# Private_CPU_IO.net
KiCad netlist of a schematic drawn in Altium Designer
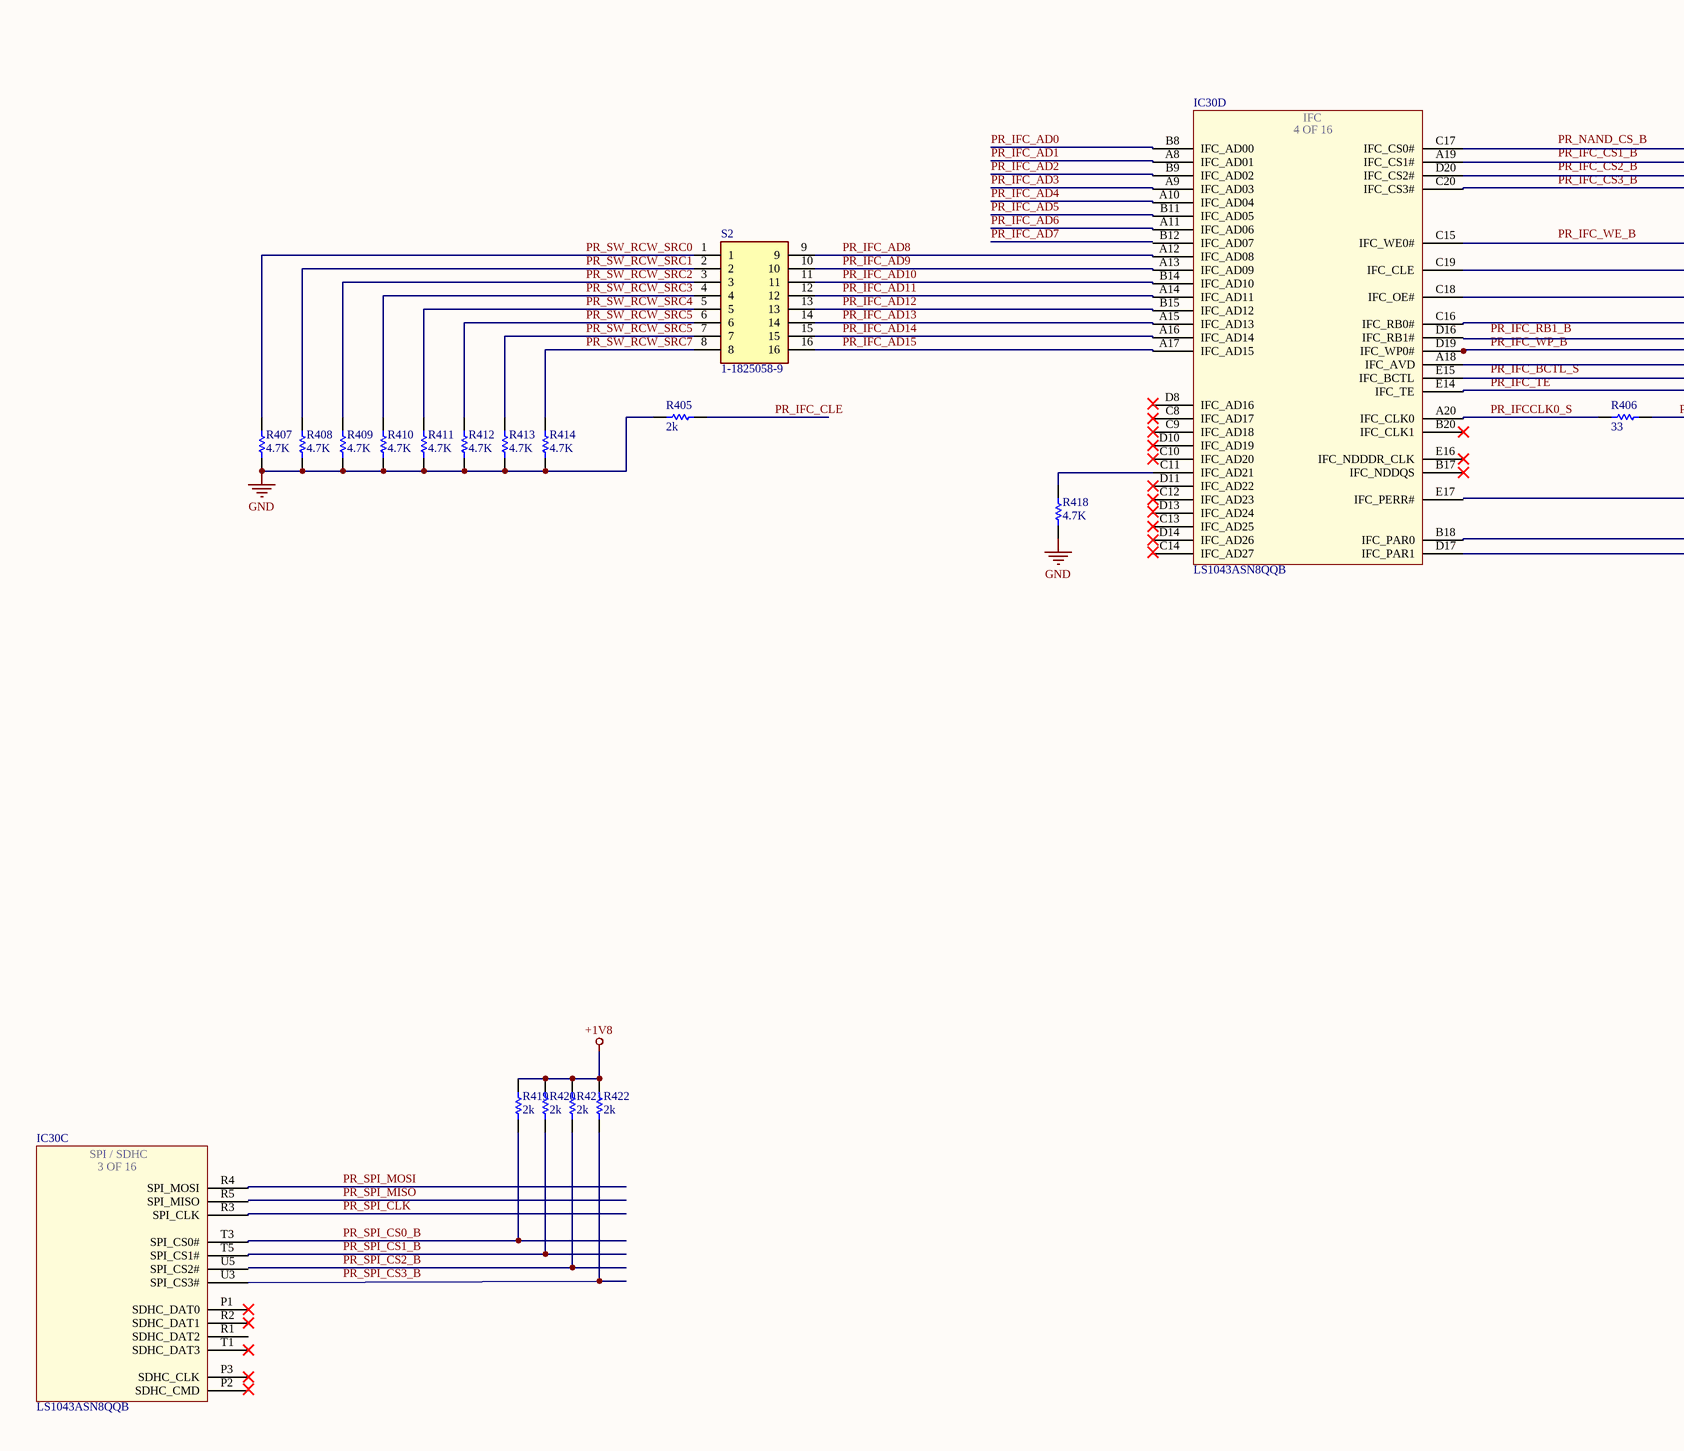
[diagram p0: Private_CPU_IO.SchDoc, left]
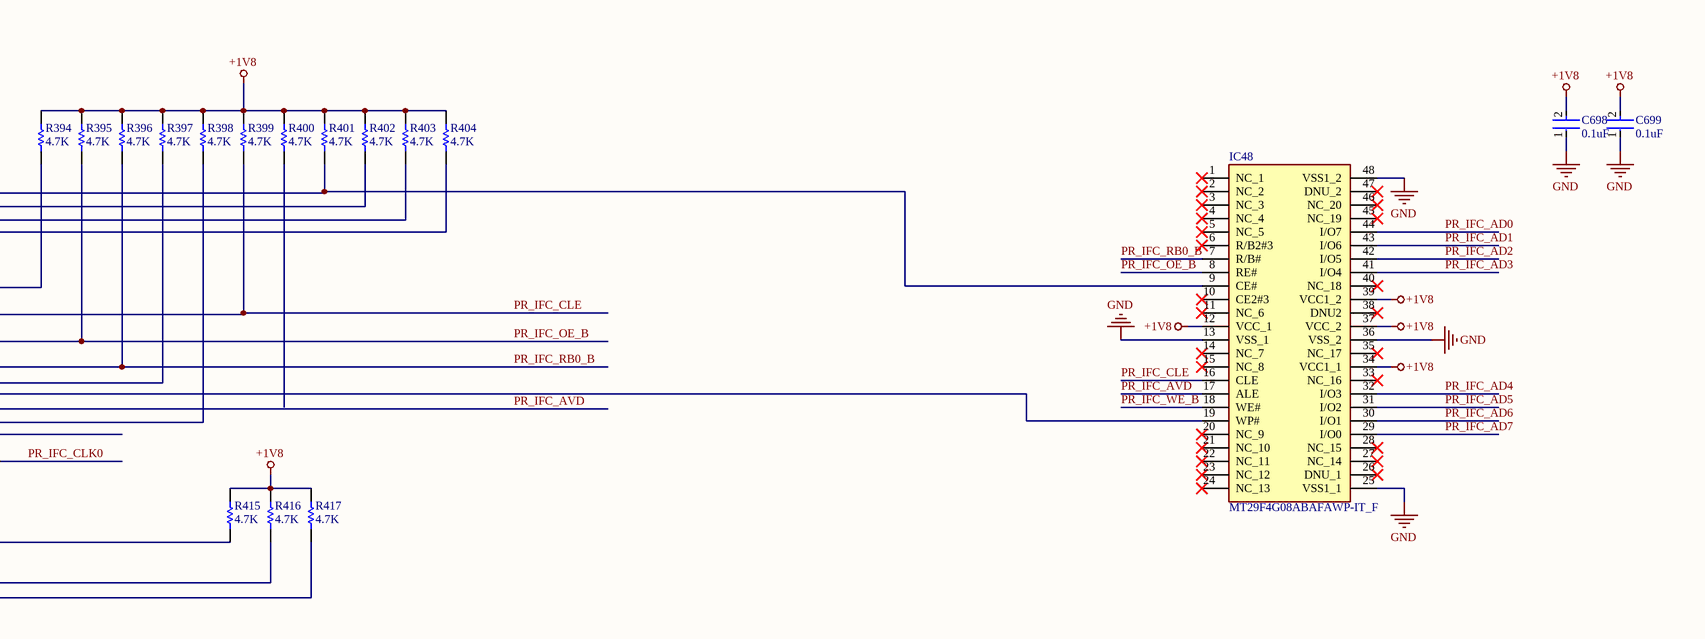
[diagram p1: Private_CPU_IO.SchDoc, right]

(export (version "E")
  (design (tool "Eeschema 10.0.6"))
  (components
    (comp (ref "C698")
      (value "0.1uF")
      (footprint "FP-GRM15-MFG")
      (description "CAP CER 0.1UF 16V X7R 0402")
      (fields (field (name "MANUFACTURER PART NUMBER") "GRM155R71C104KA88D") (field (name "TOLERANCE") "10%"))
      (libsource (lib "Altium Content Vault") (part "236180d848d6139a670b325ea6854c9"))
    )
    (comp (ref "C699")
      (value "0.1uF")
      (footprint "FP-GRM15-MFG")
      (description "CAP CER 0.1UF 16V X7R 0402")
      (fields (field (name "MANUFACTURER PART NUMBER") "GRM155R71C104KA88D") (field (name "TOLERANCE") "10%"))
      (libsource (lib "Altium Content Vault") (part "236180d848d6139a670b325ea6854c9"))
    )
    (comp (ref "IC30")
      (value "LS1043ASN8QQB")
      (footprint "SamacSys:BGA780C80P28X28_2300X2300X261")
      (description "Integrated Circuit")
      (fields (field (name "MOUSER PART NUMBER") "771-LS1043ASN8QQB"))
      (libsource (lib "SamacSys") (part "LS1043ASN8QQB"))
    )
    (comp (ref "IC48")
      (value "MT29F4G08ABAFAWP-IT_F")
      (footprint "SamacSys:SOP50P2000X120-48N")
      (description "Integrated Circuit")
      (fields
        (field (name "MANUFACTURER_PART_NUMBER") "MT29F4G08ABAFAWP-IT:F")
        (field (name "MOUSER PART NUMBER") "340-371016-TRAY")
      )
      (libsource (lib "*") (part "MT29F4G08ABAFAWP-IT_F"))
    )
    (comp (ref "R394")
      (value "4.7K")
      (footprint "RESC1005X40X25LL05T05")
      (description "Chip Resistor, 4.7 KOhm, +/- 1%, 0.1 W, -55 to 155 degC, 0402 (1005 Metric), RoHS, Tape and Reel")
      (fields (field (name "TOLERANCE") "1%") (field (name "PARTNUMBER") "ERJ-2RKF4701X"))
      (libsource (lib "Altium Content Vault") (part "RES-2"))
    )
    (comp (ref "R395")
      (value "4.7K")
      (footprint "RESC1005X40X25LL05T05")
      (description "Chip Resistor, 4.7 KOhm, +/- 1%, 0.1 W, -55 to 155 degC, 0402 (1005 Metric), RoHS, Tape and Reel")
      (fields (field (name "TOLERANCE") "1%") (field (name "PARTNUMBER") "ERJ-2RKF4701X"))
      (libsource (lib "Altium Content Vault") (part "RES-2"))
    )
    (comp (ref "R396")
      (value "4.7K")
      (footprint "RESC1005X40X25LL05T05")
      (description "Chip Resistor, 4.7 KOhm, +/- 1%, 0.1 W, -55 to 155 degC, 0402 (1005 Metric), RoHS, Tape and Reel")
      (fields (field (name "TOLERANCE") "1%") (field (name "PARTNUMBER") "ERJ-2RKF4701X"))
      (libsource (lib "Altium Content Vault") (part "RES-2"))
    )
    (comp (ref "R397")
      (value "4.7K")
      (footprint "RESC1005X40X25LL05T05")
      (description "Chip Resistor, 4.7 KOhm, +/- 1%, 0.1 W, -55 to 155 degC, 0402 (1005 Metric), RoHS, Tape and Reel")
      (fields (field (name "TOLERANCE") "1%") (field (name "PARTNUMBER") "ERJ-2RKF4701X"))
      (libsource (lib "Altium Content Vault") (part "RES-2"))
    )
    (comp (ref "R398")
      (value "4.7K")
      (footprint "RESC1005X40X25LL05T05")
      (description "Chip Resistor, 4.7 KOhm, +/- 1%, 0.1 W, -55 to 155 degC, 0402 (1005 Metric), RoHS, Tape and Reel")
      (fields (field (name "TOLERANCE") "1%") (field (name "PARTNUMBER") "ERJ-2RKF4701X"))
      (libsource (lib "Altium Content Vault") (part "RES-2"))
    )
    (comp (ref "R399")
      (value "4.7K")
      (footprint "RESC1005X40X25LL05T05")
      (description "Chip Resistor, 4.7 KOhm, +/- 1%, 0.1 W, -55 to 155 degC, 0402 (1005 Metric), RoHS, Tape and Reel")
      (fields (field (name "TOLERANCE") "1%") (field (name "PARTNUMBER") "ERJ-2RKF4701X"))
      (libsource (lib "Altium Content Vault") (part "RES-2"))
    )
    (comp (ref "R400")
      (value "4.7K")
      (footprint "RESC1005X40X25LL05T05")
      (description "Chip Resistor, 4.7 KOhm, +/- 1%, 0.1 W, -55 to 155 degC, 0402 (1005 Metric), RoHS, Tape and Reel")
      (fields (field (name "TOLERANCE") "1%") (field (name "PARTNUMBER") "ERJ-2RKF4701X"))
      (libsource (lib "Altium Content Vault") (part "RES-2"))
    )
    (comp (ref "R401")
      (value "4.7K")
      (footprint "RESC1005X40X25LL05T05")
      (description "Chip Resistor, 4.7 KOhm, +/- 1%, 0.1 W, -55 to 155 degC, 0402 (1005 Metric), RoHS, Tape and Reel")
      (fields (field (name "TOLERANCE") "1%") (field (name "PARTNUMBER") "ERJ-2RKF4701X"))
      (libsource (lib "Altium Content Vault") (part "RES-2"))
    )
    (comp (ref "R402")
      (value "4.7K")
      (footprint "RESC1005X40X25LL05T05")
      (description "Chip Resistor, 4.7 KOhm, +/- 1%, 0.1 W, -55 to 155 degC, 0402 (1005 Metric), RoHS, Tape and Reel")
      (fields (field (name "TOLERANCE") "1%") (field (name "PARTNUMBER") "ERJ-2RKF4701X"))
      (libsource (lib "Altium Content Vault") (part "RES-2"))
    )
    (comp (ref "R403")
      (value "4.7K")
      (footprint "RESC1005X40X25LL05T05")
      (description "Chip Resistor, 4.7 KOhm, +/- 1%, 0.1 W, -55 to 155 degC, 0402 (1005 Metric), RoHS, Tape and Reel")
      (fields (field (name "TOLERANCE") "1%") (field (name "PARTNUMBER") "ERJ-2RKF4701X"))
      (libsource (lib "Altium Content Vault") (part "RES-2"))
    )
    (comp (ref "R404")
      (value "4.7K")
      (footprint "RESC1005X40X25LL05T05")
      (description "Chip Resistor, 4.7 KOhm, +/- 1%, 0.1 W, -55 to 155 degC, 0402 (1005 Metric), RoHS, Tape and Reel")
      (fields (field (name "TOLERANCE") "1%") (field (name "PARTNUMBER") "ERJ-2RKF4701X"))
      (libsource (lib "Altium Content Vault") (part "RES-2"))
    )
    (comp (ref "R405")
      (value "2k")
      (footprint "RESC1005X40X25NL05T05")
      (description "Chip Resistor, 2 KOhm, +/- 1%, 100 mW, -55 to 155 degC, 0402 (1005 Metric), RoHS, Tape and Reel")
      (fields (field (name "MANUFACTURER") "Basic Passives") (field (name "TOLERANCE") "1%"))
      (libsource (lib "Altium Content Vault") (part "RES-2"))
    )
    (comp (ref "R406")
      (value "33")
      (footprint "RESC1005X40X25LL05T05")
      (fields (field (name "MANUFACTURER") "Panasonic") (field (name "PART NUMBER") "ERJ2RKF33R0X"))
      (libsource (lib "Altium Content Vault") (part "RES"))
    )
    (comp (ref "R407")
      (value "4.7K")
      (footprint "RESC1005X40X25LL05T05")
      (description "Chip Resistor, 4.7 KOhm, +/- 1%, 0.1 W, -55 to 155 degC, 0402 (1005 Metric), RoHS, Tape and Reel")
      (fields (field (name "TOLERANCE") "1%") (field (name "PARTNUMBER") "ERJ-2RKF4701X"))
      (libsource (lib "Altium Content Vault") (part "RES-2"))
    )
    (comp (ref "R408")
      (value "4.7K")
      (footprint "RESC1005X40X25LL05T05")
      (description "Chip Resistor, 4.7 KOhm, +/- 1%, 0.1 W, -55 to 155 degC, 0402 (1005 Metric), RoHS, Tape and Reel")
      (fields (field (name "TOLERANCE") "1%") (field (name "PARTNUMBER") "ERJ-2RKF4701X"))
      (libsource (lib "Altium Content Vault") (part "RES-2"))
    )
    (comp (ref "R409")
      (value "4.7K")
      (footprint "RESC1005X40X25LL05T05")
      (description "Chip Resistor, 4.7 KOhm, +/- 1%, 0.1 W, -55 to 155 degC, 0402 (1005 Metric), RoHS, Tape and Reel")
      (fields (field (name "TOLERANCE") "1%") (field (name "PARTNUMBER") "ERJ-2RKF4701X"))
      (libsource (lib "Altium Content Vault") (part "RES-2"))
    )
    (comp (ref "R410")
      (value "4.7K")
      (footprint "RESC1005X40X25LL05T05")
      (description "Chip Resistor, 4.7 KOhm, +/- 1%, 0.1 W, -55 to 155 degC, 0402 (1005 Metric), RoHS, Tape and Reel")
      (fields (field (name "TOLERANCE") "1%") (field (name "PARTNUMBER") "ERJ-2RKF4701X"))
      (libsource (lib "Altium Content Vault") (part "RES-2"))
    )
    (comp (ref "R411")
      (value "4.7K")
      (footprint "RESC1005X40X25LL05T05")
      (description "Chip Resistor, 4.7 KOhm, +/- 1%, 0.1 W, -55 to 155 degC, 0402 (1005 Metric), RoHS, Tape and Reel")
      (fields (field (name "TOLERANCE") "1%") (field (name "PARTNUMBER") "ERJ-2RKF4701X"))
      (libsource (lib "Altium Content Vault") (part "RES-2"))
    )
    (comp (ref "R412")
      (value "4.7K")
      (footprint "RESC1005X40X25LL05T05")
      (description "Chip Resistor, 4.7 KOhm, +/- 1%, 0.1 W, -55 to 155 degC, 0402 (1005 Metric), RoHS, Tape and Reel")
      (fields (field (name "TOLERANCE") "1%") (field (name "PARTNUMBER") "ERJ-2RKF4701X"))
      (libsource (lib "Altium Content Vault") (part "RES-2"))
    )
    (comp (ref "R413")
      (value "4.7K")
      (footprint "RESC1005X40X25LL05T05")
      (description "Chip Resistor, 4.7 KOhm, +/- 1%, 0.1 W, -55 to 155 degC, 0402 (1005 Metric), RoHS, Tape and Reel")
      (fields (field (name "TOLERANCE") "1%") (field (name "PARTNUMBER") "ERJ-2RKF4701X"))
      (libsource (lib "Altium Content Vault") (part "RES-2"))
    )
    (comp (ref "R414")
      (value "4.7K")
      (footprint "RESC1005X40X25LL05T05")
      (description "Chip Resistor, 4.7 KOhm, +/- 1%, 0.1 W, -55 to 155 degC, 0402 (1005 Metric), RoHS, Tape and Reel")
      (fields (field (name "TOLERANCE") "1%") (field (name "PARTNUMBER") "ERJ-2RKF4701X"))
      (libsource (lib "Altium Content Vault") (part "RES-2"))
    )
    (comp (ref "R415")
      (value "4.7K")
      (footprint "RESC1005X40X25LL05T05")
      (description "Chip Resistor, 4.7 KOhm, +/- 1%, 0.1 W, -55 to 155 degC, 0402 (1005 Metric), RoHS, Tape and Reel")
      (fields (field (name "TOLERANCE") "1%") (field (name "PARTNUMBER") "ERJ-2RKF4701X"))
      (libsource (lib "Altium Content Vault") (part "RES-2"))
    )
    (comp (ref "R416")
      (value "4.7K")
      (footprint "RESC1005X40X25LL05T05")
      (description "Chip Resistor, 4.7 KOhm, +/- 1%, 0.1 W, -55 to 155 degC, 0402 (1005 Metric), RoHS, Tape and Reel")
      (fields (field (name "TOLERANCE") "1%") (field (name "PARTNUMBER") "ERJ-2RKF4701X"))
      (libsource (lib "Altium Content Vault") (part "RES-2"))
    )
    (comp (ref "R417")
      (value "4.7K")
      (footprint "RESC1005X40X25LL05T05")
      (description "Chip Resistor, 4.7 KOhm, +/- 1%, 0.1 W, -55 to 155 degC, 0402 (1005 Metric), RoHS, Tape and Reel")
      (fields (field (name "TOLERANCE") "1%") (field (name "PARTNUMBER") "ERJ-2RKF4701X"))
      (libsource (lib "Altium Content Vault") (part "RES-2"))
    )
    (comp (ref "R418")
      (value "4.7K")
      (footprint "RESC1005X40X25LL05T05")
      (description "Chip Resistor, 4.7 KOhm, +/- 1%, 0.1 W, -55 to 155 degC, 0402 (1005 Metric), RoHS, Tape and Reel")
      (fields (field (name "TOLERANCE") "1%") (field (name "PARTNUMBER") "ERJ-2RKF4701X"))
      (libsource (lib "Altium Content Vault") (part "RES-2"))
    )
    (comp (ref "R419")
      (value "2k")
      (footprint "RESC1005X40X25NL05T05")
      (description "Chip Resistor, 2 KOhm, +/- 1%, 100 mW, -55 to 155 degC, 0402 (1005 Metric), RoHS, Tape and Reel")
      (fields (field (name "MANUFACTURER") "Basic Passives") (field (name "TOLERANCE") "1%"))
      (libsource (lib "Altium Content Vault") (part "RES-2"))
    )
    (comp (ref "R420")
      (value "2k")
      (footprint "RESC1005X40X25NL05T05")
      (description "Chip Resistor, 2 KOhm, +/- 1%, 100 mW, -55 to 155 degC, 0402 (1005 Metric), RoHS, Tape and Reel")
      (fields (field (name "MANUFACTURER") "Basic Passives") (field (name "TOLERANCE") "1%"))
      (libsource (lib "Altium Content Vault") (part "RES-2"))
    )
    (comp (ref "R421")
      (value "2k")
      (footprint "RESC1005X40X25NL05T05")
      (description "Chip Resistor, 2 KOhm, +/- 1%, 100 mW, -55 to 155 degC, 0402 (1005 Metric), RoHS, Tape and Reel")
      (fields (field (name "MANUFACTURER") "Basic Passives") (field (name "TOLERANCE") "1%"))
      (libsource (lib "Altium Content Vault") (part "RES-2"))
    )
    (comp (ref "R422")
      (value "2k")
      (footprint "RESC1005X40X25NL05T05")
      (description "Chip Resistor, 2 KOhm, +/- 1%, 100 mW, -55 to 155 degC, 0402 (1005 Metric), RoHS, Tape and Reel")
      (fields (field (name "MANUFACTURER") "Basic Passives") (field (name "TOLERANCE") "1%"))
      (libsource (lib "Altium Content Vault") (part "RES-2"))
    )
    (comp (ref "S2")
      (value "1-1825058-9")
      (footprint "SamacSys:118250589")
      (description "Switch")
      (libsource (lib "*") (part "1-1825058-9"))
    )
  )
  (nets
    (net (code "1") (name "+1V8") (class "Default")
      (node (ref "C698") (pin "2") (pinfunction "2_2") (pintype "passive"))
      (node (ref "C699") (pin "2") (pinfunction "2_2") (pintype "passive"))
      (node (ref "IC48") (pin "12") (pinfunction "VCC_1_12") (pintype "passive"))
      (node (ref "IC48") (pin "34") (pinfunction "VCC1_1_34") (pintype "passive"))
      (node (ref "IC48") (pin "37") (pinfunction "VCC_2_37") (pintype "passive"))
      (node (ref "IC48") (pin "39") (pinfunction "VCC1_2_39") (pintype "passive"))
      (node (ref "R394") (pin "2") (pinfunction "2_2") (pintype "passive"))
      (node (ref "R395") (pin "2") (pinfunction "2_2") (pintype "passive"))
      (node (ref "R396") (pin "2") (pinfunction "2_2") (pintype "passive"))
      (node (ref "R397") (pin "2") (pinfunction "2_2") (pintype "passive"))
      (node (ref "R398") (pin "2") (pinfunction "2_2") (pintype "passive"))
      (node (ref "R399") (pin "2") (pinfunction "2_2") (pintype "passive"))
      (node (ref "R400") (pin "2") (pinfunction "2_2") (pintype "passive"))
      (node (ref "R401") (pin "2") (pinfunction "2_2") (pintype "passive"))
      (node (ref "R402") (pin "2") (pinfunction "2_2") (pintype "passive"))
      (node (ref "R403") (pin "2") (pinfunction "2_2") (pintype "passive"))
      (node (ref "R404") (pin "2") (pinfunction "2_2") (pintype "passive"))
      (node (ref "R415") (pin "2") (pinfunction "2_2") (pintype "passive"))
      (node (ref "R416") (pin "2") (pinfunction "2_2") (pintype "passive"))
      (node (ref "R417") (pin "2") (pinfunction "2_2") (pintype "passive"))
      (node (ref "R419") (pin "1") (pinfunction "1_1") (pintype "passive"))
      (node (ref "R420") (pin "1") (pinfunction "1_1") (pintype "passive"))
      (node (ref "R421") (pin "1") (pinfunction "1_1") (pintype "passive"))
      (node (ref "R422") (pin "1") (pinfunction "1_1") (pintype "passive"))
    )
    (net (code "2") (name "/PR_IFCCLK0_S") (class "Default")
      (node (ref "IC30") (pin "A20") (pinfunction "IFC_CLK0_A20") (pintype "passive"))
      (node (ref "R406") (pin "1") (pinfunction "1_1") (pintype "passive"))
    )
    (net (code "3") (name "/PR_IFC_AD0") (class "Default")
      (node (ref "IC30") (pin "B8") (pinfunction "IFC_AD00_B8") (pintype "passive"))
      (node (ref "IC48") (pin "44") (pinfunction "I/O7_44") (pintype "passive"))
    )
    (net (code "4") (name "/PR_IFC_AD1") (class "Default")
      (node (ref "IC30") (pin "A8") (pinfunction "IFC_AD01_A8") (pintype "passive"))
      (node (ref "IC48") (pin "43") (pinfunction "I/O6_43") (pintype "passive"))
    )
    (net (code "5") (name "/PR_IFC_AD2") (class "Default")
      (node (ref "IC30") (pin "B9") (pinfunction "IFC_AD02_B9") (pintype "passive"))
      (node (ref "IC48") (pin "42") (pinfunction "I/O5_42") (pintype "passive"))
    )
    (net (code "6") (name "/PR_IFC_AD3") (class "Default")
      (node (ref "IC30") (pin "A9") (pinfunction "IFC_AD03_A9") (pintype "passive"))
      (node (ref "IC48") (pin "41") (pinfunction "I/O4_41") (pintype "passive"))
    )
    (net (code "7") (name "/PR_IFC_AD4") (class "Default")
      (node (ref "IC30") (pin "A10") (pinfunction "IFC_AD04_A10") (pintype "passive"))
      (node (ref "IC48") (pin "32") (pinfunction "I/O3_32") (pintype "passive"))
    )
    (net (code "8") (name "/PR_IFC_AD5") (class "Default")
      (node (ref "IC30") (pin "B11") (pinfunction "IFC_AD05_B11") (pintype "passive"))
      (node (ref "IC48") (pin "31") (pinfunction "I/O2_31") (pintype "passive"))
    )
    (net (code "9") (name "/PR_IFC_AD6") (class "Default")
      (node (ref "IC30") (pin "A11") (pinfunction "IFC_AD06_A11") (pintype "passive"))
      (node (ref "IC48") (pin "30") (pinfunction "I/O1_30") (pintype "passive"))
    )
    (net (code "10") (name "/PR_IFC_AD7") (class "Default")
      (node (ref "IC48") (pin "29") (pinfunction "I/O0_29") (pintype "passive"))
    )
    (net (code "11") (name "/PR_IFC_AD8") (class "Default")
      (node (ref "IC30") (pin "A12") (pinfunction "IFC_AD08_A12") (pintype "passive"))
      (node (ref "S2") (pin "9") (pinfunction "9_9") (pintype "passive"))
    )
    (net (code "12") (name "/PR_IFC_AD9") (class "Default")
      (node (ref "IC30") (pin "A13") (pinfunction "IFC_AD09_A13") (pintype "passive"))
      (node (ref "S2") (pin "10") (pinfunction "10_10") (pintype "passive"))
    )
    (net (code "13") (name "/PR_IFC_AD10") (class "Default")
      (node (ref "IC30") (pin "B14") (pinfunction "IFC_AD10_B14") (pintype "passive"))
      (node (ref "S2") (pin "11") (pinfunction "11_11") (pintype "passive"))
    )
    (net (code "14") (name "/PR_IFC_AD11") (class "Default")
      (node (ref "IC30") (pin "A14") (pinfunction "IFC_AD11_A14") (pintype "passive"))
      (node (ref "S2") (pin "12") (pinfunction "12_12") (pintype "passive"))
    )
    (net (code "15") (name "/PR_IFC_AD12") (class "Default")
      (node (ref "IC30") (pin "B15") (pinfunction "IFC_AD12_B15") (pintype "passive"))
      (node (ref "S2") (pin "13") (pinfunction "13_13") (pintype "passive"))
    )
    (net (code "16") (name "/PR_IFC_AD13") (class "Default")
      (node (ref "IC30") (pin "A15") (pinfunction "IFC_AD13_A15") (pintype "passive"))
      (node (ref "S2") (pin "14") (pinfunction "14_14") (pintype "passive"))
    )
    (net (code "17") (name "/PR_IFC_AD14") (class "Default")
      (node (ref "IC30") (pin "A16") (pinfunction "IFC_AD14_A16") (pintype "passive"))
      (node (ref "S2") (pin "15") (pinfunction "15_15") (pintype "passive"))
    )
    (net (code "18") (name "/PR_IFC_AD15") (class "Default")
      (node (ref "IC30") (pin "A17") (pinfunction "IFC_AD15_A17") (pintype "passive"))
      (node (ref "S2") (pin "16") (pinfunction "16_16") (pintype "passive"))
    )
    (net (code "19") (name "/PR_IFC_AVD") (class "Default")
      (node (ref "IC30") (pin "A18") (pinfunction "IFC_AVD_A18") (pintype "passive"))
      (node (ref "IC48") (pin "17") (pinfunction "ALE_17") (pintype "passive"))
    )
    (net (code "21") (name "/PR_IFC_CLE") (class "Default")
      (node (ref "IC30") (pin "C19") (pinfunction "IFC_CLE_C19") (pintype "passive"))
      (node (ref "IC48") (pin "16") (pinfunction "CLE_16") (pintype "passive"))
      (node (ref "R399") (pin "1") (pinfunction "1_1") (pintype "passive"))
      (node (ref "R405") (pin "1") (pinfunction "1_1") (pintype "passive"))
    )
    (net (code "22") (name "/PR_IFC_CLK0") (class "Default")
      (node (ref "R406") (pin "2") (pinfunction "2_2") (pintype "passive"))
    )
    (net (code "25") (name "/PR_IFC_CS3_B") (class "Default")
      (node (ref "IC30") (pin "C20") (pinfunction "IFC_CS3#_C20") (pintype "passive"))
      (node (ref "R404") (pin "1") (pinfunction "1_1") (pintype "passive"))
    )
    (net (code "26") (name "/PR_IFC_OE_B") (class "Default")
      (node (ref "IC30") (pin "C18") (pinfunction "IFC_OE#_C18") (pintype "passive"))
      (node (ref "IC48") (pin "8") (pinfunction "RE#_8") (pintype "passive"))
      (node (ref "R395") (pin "1") (pinfunction "1_1") (pintype "passive"))
    )
    (net (code "27") (name "/PR_IFC_RB0_B") (class "Default")
      (node (ref "IC30") (pin "C16") (pinfunction "IFC_RB0#_C16") (pintype "passive"))
      (node (ref "IC48") (pin "7") (pinfunction "R/B#_7") (pintype "passive"))
      (node (ref "R396") (pin "1") (pinfunction "1_1") (pintype "passive"))
    )
    (net (code "29") (name "/PR_IFC_TE") (class "Default")
      (node (ref "IC30") (pin "E14") (pinfunction "IFC_TE_E14") (pintype "passive"))
    )
    (net (code "30") (name "/PR_IFC_WE_B") (class "Default")
      (node (ref "IC48") (pin "18") (pinfunction "WE#_18") (pintype "passive"))
    )
    (net (code "31") (name "/PR_IFC_WP_B") (class "Default")
      (node (ref "IC30") (pin "D19") (pinfunction "IFC_WP0#_D19") (pintype "passive"))
      (node (ref "IC48") (pin "19") (pinfunction "WP#_19") (pintype "passive"))
    )
    (net (code "33") (name "/PR_SPI_CLK") (class "Default")
      (node (ref "IC30") (pin "R3") (pinfunction "SPI_CLK_R3") (pintype "passive"))
    )
    (net (code "34") (name "/PR_SPI_CS0_B") (class "Default")
      (node (ref "IC30") (pin "T3") (pinfunction "SPI_CS0#_T3") (pintype "passive"))
      (node (ref "R419") (pin "2") (pinfunction "2_2") (pintype "passive"))
    )
    (net (code "35") (name "/PR_SPI_CS1_B") (class "Default")
      (node (ref "IC30") (pin "T5") (pinfunction "SPI_CS1#_T5") (pintype "passive"))
      (node (ref "R420") (pin "2") (pinfunction "2_2") (pintype "passive"))
    )
    (net (code "36") (name "/PR_SPI_CS2_B") (class "Default")
      (node (ref "R421") (pin "2") (pinfunction "2_2") (pintype "passive"))
    )
    (net (code "39") (name "/PR_SPI_MOSI") (class "Default")
      (node (ref "IC30") (pin "R4") (pinfunction "SPI_MOSI_R4") (pintype "passive"))
    )
    (net (code "40") (name "/PR_SW_RCW_SRC0") (class "Default")
      (node (ref "R407") (pin "2") (pinfunction "2_2") (pintype "passive"))
      (node (ref "S2") (pin "1") (pinfunction "1_1") (pintype "passive"))
    )
    (net (code "41") (name "/PR_SW_RCW_SRC1") (class "Default")
      (node (ref "R408") (pin "2") (pinfunction "2_2") (pintype "passive"))
      (node (ref "S2") (pin "2") (pinfunction "2_2") (pintype "passive"))
    )
    (net (code "42") (name "/PR_SW_RCW_SRC2") (class "Default")
      (node (ref "R409") (pin "2") (pinfunction "2_2") (pintype "passive"))
      (node (ref "S2") (pin "3") (pinfunction "3_3") (pintype "passive"))
    )
    (net (code "43") (name "/PR_SW_RCW_SRC3") (class "Default")
      (node (ref "R410") (pin "2") (pinfunction "2_2") (pintype "passive"))
      (node (ref "S2") (pin "4") (pinfunction "4_4") (pintype "passive"))
    )
    (net (code "44") (name "/PR_SW_RCW_SRC4") (class "Default")
      (node (ref "R411") (pin "2") (pinfunction "2_2") (pintype "passive"))
      (node (ref "S2") (pin "5") (pinfunction "5_5") (pintype "passive"))
    )
    (net (code "45") (name "/PR_SW_RCW_SRC5") (class "Default")
      (node (ref "R412") (pin "2") (pinfunction "2_2") (pintype "passive"))
      (node (ref "R413") (pin "2") (pinfunction "2_2") (pintype "passive"))
      (node (ref "S2") (pin "6") (pinfunction "6_6") (pintype "passive"))
      (node (ref "S2") (pin "7") (pinfunction "7_7") (pintype "passive"))
    )
    (net (code "46") (name "/PR_SW_RCW_SRC7") (class "Default")
      (node (ref "R414") (pin "2") (pinfunction "2_2") (pintype "passive"))
      (node (ref "S2") (pin "8") (pinfunction "8_8") (pintype "passive"))
    )
    (net (code "47") (name "GND") (class "Default")
      (node (ref "C698") (pin "1") (pinfunction "1_1") (pintype "passive"))
      (node (ref "C699") (pin "1") (pinfunction "1_1") (pintype "passive"))
      (node (ref "IC48") (pin "13") (pinfunction "VSS_1_13") (pintype "passive"))
      (node (ref "IC48") (pin "25") (pinfunction "VSS1_1_25") (pintype "passive"))
      (node (ref "IC48") (pin "36") (pinfunction "VSS_2_36") (pintype "passive"))
      (node (ref "IC48") (pin "48") (pinfunction "VSS1_2_48") (pintype "passive"))
      (node (ref "R405") (pin "2") (pinfunction "2_2") (pintype "passive"))
      (node (ref "R407") (pin "1") (pinfunction "1_1") (pintype "passive"))
      (node (ref "R408") (pin "1") (pinfunction "1_1") (pintype "passive"))
      (node (ref "R409") (pin "1") (pinfunction "1_1") (pintype "passive"))
      (node (ref "R410") (pin "1") (pinfunction "1_1") (pintype "passive"))
      (node (ref "R411") (pin "1") (pinfunction "1_1") (pintype "passive"))
      (node (ref "R412") (pin "1") (pinfunction "1_1") (pintype "passive"))
      (node (ref "R413") (pin "1") (pinfunction "1_1") (pintype "passive"))
      (node (ref "R414") (pin "1") (pinfunction "1_1") (pintype "passive"))
      (node (ref "R418") (pin "1") (pinfunction "1_1") (pintype "passive"))
    )
    (net (code "48") (name "Net-(IC30C-SPI_CS3#)") (class "Default")
      (node (ref "IC30") (pin "U3") (pinfunction "SPI_CS3#_U3") (pintype "passive"))
      (node (ref "R422") (pin "2") (pinfunction "2_2") (pintype "passive"))
    )
    (net (code "49") (name "Net-(IC30D-IFC_AD21)") (class "Default")
      (node (ref "IC30") (pin "C11") (pinfunction "IFC_AD21_C11") (pintype "passive"))
      (node (ref "R418") (pin "2") (pinfunction "2_2") (pintype "passive"))
    )
    (net (code "50") (name "Net-(IC30D-IFC_BCTL)") (class "Default")
      (node (ref "IC30") (pin "E15") (pinfunction "IFC_BCTL_E15") (pintype "passive"))
      (node (ref "R398") (pin "1") (pinfunction "1_1") (pintype "passive"))
    )
    (net (code "51") (name "Net-(IC30D-IFC_CS0#)") (class "Default")
      (node (ref "IC30") (pin "C17") (pinfunction "IFC_CS0#_C17") (pintype "passive"))
      (node (ref "IC48") (pin "9") (pinfunction "CE#_9") (pintype "passive"))
      (node (ref "R401") (pin "1") (pinfunction "1_1") (pintype "passive"))
    )
    (net (code "52") (name "Net-(IC30D-IFC_CS1#)") (class "Default")
      (node (ref "IC30") (pin "A19") (pinfunction "IFC_CS1#_A19") (pintype "passive"))
      (node (ref "R402") (pin "1") (pinfunction "1_1") (pintype "passive"))
    )
    (net (code "53") (name "Net-(IC30D-IFC_CS2#)") (class "Default")
      (node (ref "IC30") (pin "D20") (pinfunction "IFC_CS2#_D20") (pintype "passive"))
      (node (ref "R403") (pin "1") (pinfunction "1_1") (pintype "passive"))
    )
    (net (code "54") (name "Net-(IC30D-IFC_PAR0)") (class "Default")
      (node (ref "IC30") (pin "B18") (pinfunction "IFC_PAR0_B18") (pintype "passive"))
      (node (ref "R416") (pin "1") (pinfunction "1_1") (pintype "passive"))
    )
    (net (code "55") (name "Net-(IC30D-IFC_PAR1)") (class "Default")
      (node (ref "IC30") (pin "D17") (pinfunction "IFC_PAR1_D17") (pintype "passive"))
      (node (ref "R417") (pin "1") (pinfunction "1_1") (pintype "passive"))
    )
    (net (code "56") (name "Net-(IC30D-IFC_WE0#)") (class "Default")
      (node (ref "IC30") (pin "C15") (pinfunction "IFC_WE0#_C15") (pintype "passive"))
      (node (ref "R394") (pin "1") (pinfunction "1_1") (pintype "passive"))
    )
    (net (code "57") (name "unconnected-(IC30C-SDHC_CLK-PadP3)") (class "Default")
      (node (ref "IC30") (pin "P3") (pinfunction "SDHC_CLK_P3") (pintype "passive+no_connect"))
    )
    (net (code "58") (name "unconnected-(IC30C-SDHC_CMD-PadP2)") (class "Default")
      (node (ref "IC30") (pin "P2") (pinfunction "SDHC_CMD_P2") (pintype "passive"))
    )
    (net (code "59") (name "unconnected-(IC30C-SDHC_DAT0-PadP1)") (class "Default")
      (node (ref "IC30") (pin "P1") (pinfunction "SDHC_DAT0_P1") (pintype "passive+no_connect"))
    )
    (net (code "60") (name "unconnected-(IC30C-SDHC_DAT1-PadR2)") (class "Default")
      (node (ref "IC30") (pin "R2") (pinfunction "SDHC_DAT1_R2") (pintype "passive+no_connect"))
    )
    (net (code "61") (name "unconnected-(IC30C-SDHC_DAT2-PadR1)") (class "Default")
      (node (ref "IC30") (pin "R1") (pinfunction "SDHC_DAT2_R1") (pintype "passive"))
    )
    (net (code "62") (name "unconnected-(IC30C-SDHC_DAT3-PadT1)") (class "Default")
      (node (ref "IC30") (pin "T1") (pinfunction "SDHC_DAT3_T1") (pintype "passive+no_connect"))
    )
    (net (code "63") (name "unconnected-(IC30C-SPI_CS2#-PadU5)") (class "Default")
      (node (ref "IC30") (pin "U5") (pinfunction "SPI_CS2#_U5") (pintype "passive"))
    )
    (net (code "64") (name "unconnected-(IC30C-SPI_MISO-PadR5)") (class "Default")
      (node (ref "IC30") (pin "R5") (pinfunction "SPI_MISO_R5") (pintype "passive"))
    )
    (net (code "65") (name "unconnected-(IC30D-IFC_AD07-PadB12)") (class "Default")
      (node (ref "IC30") (pin "B12") (pinfunction "IFC_AD07_B12") (pintype "passive"))
    )
    (net (code "66") (name "unconnected-(IC30D-IFC_AD16-PadD8)") (class "Default")
      (node (ref "IC30") (pin "D8") (pinfunction "IFC_AD16_D8") (pintype "passive"))
    )
    (net (code "67") (name "unconnected-(IC30D-IFC_AD17-PadC8)") (class "Default")
      (node (ref "IC30") (pin "C8") (pinfunction "IFC_AD17_C8") (pintype "passive+no_connect"))
    )
    (net (code "68") (name "unconnected-(IC30D-IFC_AD18-PadC9)") (class "Default")
      (node (ref "IC30") (pin "C9") (pinfunction "IFC_AD18_C9") (pintype "passive+no_connect"))
    )
    (net (code "69") (name "unconnected-(IC30D-IFC_AD19-PadD10)") (class "Default")
      (node (ref "IC30") (pin "D10") (pinfunction "IFC_AD19_D10") (pintype "passive+no_connect"))
    )
    (net (code "70") (name "unconnected-(IC30D-IFC_AD20-PadC10)") (class "Default")
      (node (ref "IC30") (pin "C10") (pinfunction "IFC_AD20_C10") (pintype "passive+no_connect"))
    )
    (net (code "71") (name "unconnected-(IC30D-IFC_AD22-PadD11)") (class "Default")
      (node (ref "IC30") (pin "D11") (pinfunction "IFC_AD22_D11") (pintype "passive+no_connect"))
    )
    (net (code "72") (name "unconnected-(IC30D-IFC_AD23-PadC12)") (class "Default")
      (node (ref "IC30") (pin "C12") (pinfunction "IFC_AD23_C12") (pintype "passive+no_connect"))
    )
    (net (code "73") (name "unconnected-(IC30D-IFC_AD24-PadD13)") (class "Default")
      (node (ref "IC30") (pin "D13") (pinfunction "IFC_AD24_D13") (pintype "passive"))
    )
    (net (code "74") (name "unconnected-(IC30D-IFC_AD25-PadC13)") (class "Default")
      (node (ref "IC30") (pin "C13") (pinfunction "IFC_AD25_C13") (pintype "passive+no_connect"))
    )
    (net (code "75") (name "unconnected-(IC30D-IFC_AD26-PadD14)") (class "Default")
      (node (ref "IC30") (pin "D14") (pinfunction "IFC_AD26_D14") (pintype "passive+no_connect"))
    )
    (net (code "76") (name "unconnected-(IC30D-IFC_AD27-PadC14)") (class "Default")
      (node (ref "IC30") (pin "C14") (pinfunction "IFC_AD27_C14") (pintype "passive"))
    )
    (net (code "77") (name "unconnected-(IC30D-IFC_CLK1-PadB20)") (class "Default")
      (node (ref "IC30") (pin "B20") (pinfunction "IFC_CLK1_B20") (pintype "passive+no_connect"))
    )
    (net (code "78") (name "unconnected-(IC30D-IFC_NDDDR_CLK-PadE16)") (class "Default")
      (node (ref "IC30") (pin "E16") (pinfunction "IFC_NDDDR_CLK_E16") (pintype "passive+no_connect"))
    )
    (net (code "79") (name "unconnected-(IC30D-IFC_NDDQS-PadB17)") (class "Default")
      (node (ref "IC30") (pin "B17") (pinfunction "IFC_NDDQS_B17") (pintype "passive+no_connect"))
    )
    (net (code "80") (name "unconnected-(IC30D-IFC_PERR#-PadE17)") (class "Default")
      (node (ref "IC30") (pin "E17") (pinfunction "IFC_PERR#_E17") (pintype "passive"))
    )
    (net (code "81") (name "unconnected-(IC30D-IFC_RB1#-PadD16)") (class "Default")
      (node (ref "IC30") (pin "D16") (pinfunction "IFC_RB1#_D16") (pintype "passive"))
    )
    (net (code "82") (name "unconnected-(IC48-CE2#3-Pad10)") (class "Default")
      (node (ref "IC48") (pin "10") (pinfunction "CE2#3_10") (pintype "passive+no_connect"))
    )
    (net (code "83") (name "unconnected-(IC48-DNU2-Pad38)") (class "Default")
      (node (ref "IC48") (pin "38") (pinfunction "DNU2_38") (pintype "passive+no_connect"))
    )
    (net (code "84") (name "unconnected-(IC48-DNU_1-Pad26)") (class "Default")
      (node (ref "IC48") (pin "26") (pinfunction "DNU_1_26") (pintype "passive+no_connect"))
    )
    (net (code "85") (name "unconnected-(IC48-DNU_2-Pad47)") (class "Default")
      (node (ref "IC48") (pin "47") (pinfunction "DNU_2_47") (pintype "passive+no_connect"))
    )
    (net (code "86") (name "unconnected-(IC48-NC_1-Pad1)") (class "Default")
      (node (ref "IC48") (pin "1") (pinfunction "NC_1_1") (pintype "passive+no_connect"))
    )
    (net (code "87") (name "unconnected-(IC48-NC_2-Pad2)") (class "Default")
      (node (ref "IC48") (pin "2") (pinfunction "NC_2_2") (pintype "passive+no_connect"))
    )
    (net (code "88") (name "unconnected-(IC48-NC_3-Pad3)") (class "Default")
      (node (ref "IC48") (pin "3") (pinfunction "NC_3_3") (pintype "passive+no_connect"))
    )
    (net (code "89") (name "unconnected-(IC48-NC_4-Pad4)") (class "Default")
      (node (ref "IC48") (pin "4") (pinfunction "NC_4_4") (pintype "passive+no_connect"))
    )
    (net (code "90") (name "unconnected-(IC48-NC_5-Pad5)") (class "Default")
      (node (ref "IC48") (pin "5") (pinfunction "NC_5_5") (pintype "passive+no_connect"))
    )
    (net (code "91") (name "unconnected-(IC48-NC_6-Pad11)") (class "Default")
      (node (ref "IC48") (pin "11") (pinfunction "NC_6_11") (pintype "passive+no_connect"))
    )
    (net (code "92") (name "unconnected-(IC48-NC_7-Pad14)") (class "Default")
      (node (ref "IC48") (pin "14") (pinfunction "NC_7_14") (pintype "passive+no_connect"))
    )
    (net (code "93") (name "unconnected-(IC48-NC_8-Pad15)") (class "Default")
      (node (ref "IC48") (pin "15") (pinfunction "NC_8_15") (pintype "passive+no_connect"))
    )
    (net (code "94") (name "unconnected-(IC48-NC_9-Pad20)") (class "Default")
      (node (ref "IC48") (pin "20") (pinfunction "NC_9_20") (pintype "passive+no_connect"))
    )
    (net (code "95") (name "unconnected-(IC48-NC_10-Pad21)") (class "Default")
      (node (ref "IC48") (pin "21") (pinfunction "NC_10_21") (pintype "passive+no_connect"))
    )
    (net (code "96") (name "unconnected-(IC48-NC_11-Pad22)") (class "Default")
      (node (ref "IC48") (pin "22") (pinfunction "NC_11_22") (pintype "passive+no_connect"))
    )
    (net (code "97") (name "unconnected-(IC48-NC_12-Pad23)") (class "Default")
      (node (ref "IC48") (pin "23") (pinfunction "NC_12_23") (pintype "passive+no_connect"))
    )
    (net (code "98") (name "unconnected-(IC48-NC_13-Pad24)") (class "Default")
      (node (ref "IC48") (pin "24") (pinfunction "NC_13_24") (pintype "passive+no_connect"))
    )
    (net (code "99") (name "unconnected-(IC48-NC_14-Pad27)") (class "Default")
      (node (ref "IC48") (pin "27") (pinfunction "NC_14_27") (pintype "passive+no_connect"))
    )
    (net (code "100") (name "unconnected-(IC48-NC_15-Pad28)") (class "Default")
      (node (ref "IC48") (pin "28") (pinfunction "NC_15_28") (pintype "passive+no_connect"))
    )
    (net (code "101") (name "unconnected-(IC48-NC_16-Pad33)") (class "Default")
      (node (ref "IC48") (pin "33") (pinfunction "NC_16_33") (pintype "passive+no_connect"))
    )
    (net (code "102") (name "unconnected-(IC48-NC_17-Pad35)") (class "Default")
      (node (ref "IC48") (pin "35") (pinfunction "NC_17_35") (pintype "passive+no_connect"))
    )
    (net (code "103") (name "unconnected-(IC48-NC_18-Pad40)") (class "Default")
      (node (ref "IC48") (pin "40") (pinfunction "NC_18_40") (pintype "passive+no_connect"))
    )
    (net (code "104") (name "unconnected-(IC48-NC_19-Pad45)") (class "Default")
      (node (ref "IC48") (pin "45") (pinfunction "NC_19_45") (pintype "passive+no_connect"))
    )
    (net (code "105") (name "unconnected-(IC48-NC_20-Pad46)") (class "Default")
      (node (ref "IC48") (pin "46") (pinfunction "NC_20_46") (pintype "passive+no_connect"))
    )
    (net (code "106") (name "unconnected-(IC48-R{slash}B2#3-Pad6)") (class "Default")
      (node (ref "IC48") (pin "6") (pinfunction "R/B2#3_6") (pintype "passive+no_connect"))
    )
    (net (code "107") (name "unconnected-(R397-Pad1)") (class "Default")
      (node (ref "R397") (pin "1") (pinfunction "1_1") (pintype "passive"))
    )
    (net (code "108") (name "unconnected-(R400-Pad1)") (class "Default")
      (node (ref "R400") (pin "1") (pinfunction "1_1") (pintype "passive"))
    )
    (net (code "109") (name "unconnected-(R415-Pad1)") (class "Default")
      (node (ref "R415") (pin "1") (pinfunction "1_1") (pintype "passive"))
    )
  )
)
